# GBxCart_RW_v1_3_Schematic.net
KiCad netlist of a schematic drawn in EAGLE
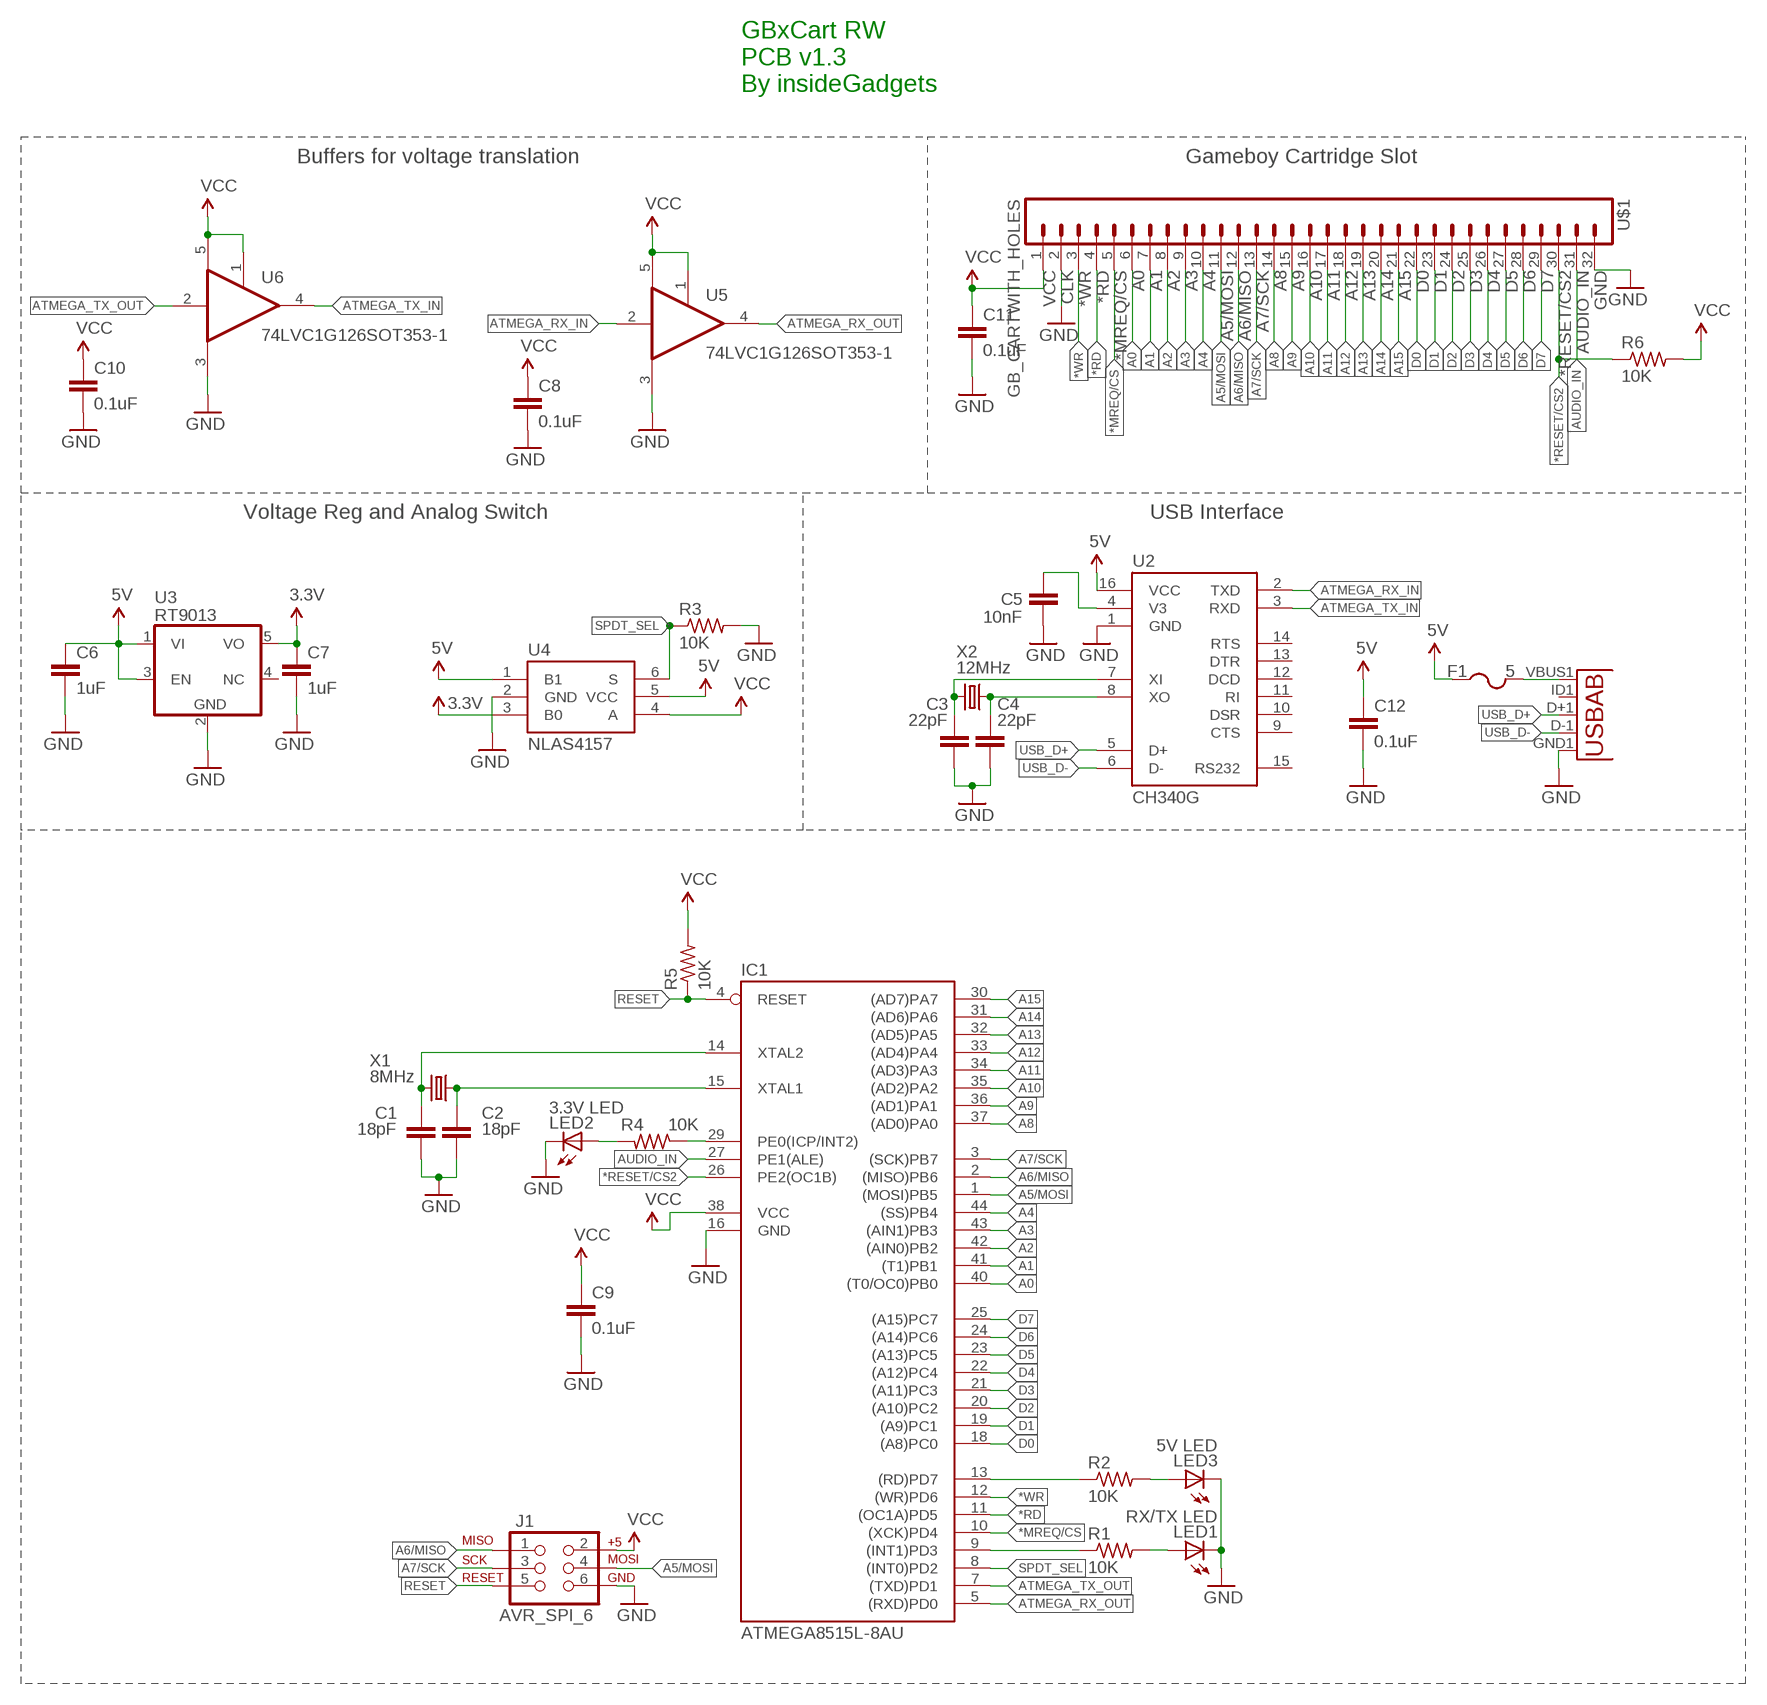
[diagram p0: schematic, sheet 1]

(export (version "E")
  (design (tool "Eeschema 10.0.6"))
  (components
    (comp (ref "C1")
      (value "18pF")
      (footprint "eagle-import:C0805K")
      (libsource (lib "eagle-import") (part "CAP0805"))
    )
    (comp (ref "C2")
      (value "18pF")
      (footprint "eagle-import:C0805K")
      (libsource (lib "eagle-import") (part "CAP0805"))
    )
    (comp (ref "C3")
      (value "22pF")
      (footprint "eagle-import:C0805K")
      (libsource (lib "eagle-import") (part "CAP0805"))
    )
    (comp (ref "C4")
      (value "22pF")
      (footprint "eagle-import:C0805K")
      (libsource (lib "eagle-import") (part "CAP0805"))
    )
    (comp (ref "C5")
      (value "10nF")
      (footprint "eagle-import:C0805K")
      (libsource (lib "eagle-import") (part "CAP0805"))
    )
    (comp (ref "C6")
      (value "1uF")
      (footprint "eagle-import:C0805K")
      (libsource (lib "eagle-import") (part "CAP0805"))
    )
    (comp (ref "C7")
      (value "1uF")
      (footprint "eagle-import:C0805K")
      (libsource (lib "eagle-import") (part "CAP0805"))
    )
    (comp (ref "C8")
      (value "0.1uF")
      (footprint "eagle-import:C0603K")
      (libsource (lib "eagle-import") (part "CAP0603"))
    )
    (comp (ref "C9")
      (value "0.1uF")
      (footprint "eagle-import:C0805K")
      (libsource (lib "eagle-import") (part "CAP0805"))
    )
    (comp (ref "C10")
      (value "0.1uF")
      (footprint "eagle-import:C0603K")
      (libsource (lib "eagle-import") (part "CAP0603"))
    )
    (comp (ref "C11")
      (value "0.1uF")
      (footprint "eagle-import:C0805K")
      (libsource (lib "eagle-import") (part "CAP0805"))
    )
    (comp (ref "C12")
      (value "0.1uF")
      (footprint "eagle-import:C0805K")
      (libsource (lib "eagle-import") (part "CAP0805"))
    )
    (comp (ref "F1")
      (value "5")
      (footprint "eagle-import:R1206")
      (libsource (lib "eagle-import") (part "PTCFUSE-1206"))
    )
    (comp (ref "IC1")
      (value "ATMEGA8515L-8AU")
      (footprint "eagle-import:TQFP44")
      (libsource (lib "eagle-import") (part "MEGA8515-A"))
    )
    (comp (ref "J1")
      (value "AVR_SPI_6")
      (footprint "eagle-import:2X3_2")
      (libsource (lib "eagle-import") (part "AVR_SPI_PRG_6"))
    )
    (comp (ref "LED1")
      (value "RX/TX LED")
      (footprint "eagle-import:CHIP-LED0805-NS")
      (libsource (lib "eagle-import") (part "LEDCHIP-LED0805-NS"))
    )
    (comp (ref "LED2")
      (value "3.3V LED")
      (footprint "eagle-import:CHIP-LED0805-NS")
      (libsource (lib "eagle-import") (part "LEDCHIP-LED0805-NS"))
    )
    (comp (ref "LED3")
      (value "5V LED")
      (footprint "eagle-import:CHIP-LED0805-NS")
      (libsource (lib "eagle-import") (part "LEDCHIP-LED0805-NS"))
    )
    (comp (ref "R1")
      (value "10K")
      (footprint "eagle-import:R0805_2")
      (libsource (lib "eagle-import") (part "R-US_R0805_2"))
    )
    (comp (ref "R2")
      (value "10K")
      (footprint "eagle-import:R0805_2")
      (libsource (lib "eagle-import") (part "R-US_R0805_2"))
    )
    (comp (ref "R3")
      (value "10K")
      (footprint "eagle-import:R0805_2")
      (libsource (lib "eagle-import") (part "R-US_R0805_2"))
    )
    (comp (ref "R4")
      (value "10K")
      (footprint "eagle-import:R0805_2")
      (libsource (lib "eagle-import") (part "R-US_R0805_2"))
    )
    (comp (ref "R5")
      (value "10K")
      (footprint "eagle-import:R0603")
      (libsource (lib "eagle-import") (part "R-US_R0603"))
    )
    (comp (ref "R6")
      (value "10K")
      (footprint "eagle-import:R0805_2")
      (libsource (lib "eagle-import") (part "R-US_R0805_2"))
    )
    (comp (ref "U$1")
      (value "GB_CARTWITH_HOLES")
      (footprint "eagle-import:GB_CART_WHOLES")
      (libsource (lib "eagle-import") (part "GB_CARTWITH_HOLES"))
    )
    (comp (ref "U1")
      (value "USBEP")
      (footprint "eagle-import:USB-MICRO-SMD-EXTRAPADS")
      (libsource (lib "eagle-import") (part "USBEP"))
    )
    (comp (ref "U2")
      (value "CH340G")
      (footprint "eagle-import:SO16")
      (libsource (lib "eagle-import") (part "CH340G"))
    )
    (comp (ref "U3")
      (value "RT9013")
      (footprint "eagle-import:SOT23-5L")
      (libsource (lib "eagle-import") (part "RT9013"))
    )
    (comp (ref "U4")
      (value "NLAS4157")
      (footprint "eagle-import:SOT363")
      (libsource (lib "eagle-import") (part "NLAS4157"))
    )
    (comp (ref "U5")
      (value "74LVC1G126SOT353-1")
      (footprint "eagle-import:SOT353-1")
      (libsource (lib "eagle-import") (part "74LVC1G126SOT353-1"))
    )
    (comp (ref "U6")
      (value "74LVC1G126SOT353-1")
      (footprint "eagle-import:SOT353-1")
      (libsource (lib "eagle-import") (part "74LVC1G126SOT353-1"))
    )
    (comp (ref "X1")
      (value "8MHz")
      (footprint "eagle-import:NX5032")
      (libsource (lib "eagle-import") (part "XTAL-5032"))
    )
    (comp (ref "X2")
      (value "12MHz")
      (footprint "eagle-import:NX5032")
      (libsource (lib "eagle-import") (part "XTAL-5032"))
    )
  )
  (nets
    (net (code "1") (name "*MREQ{slash}CS") (class "Default")
      (node (ref "IC1") (pin "10") (pinfunction "(XCK)PD4_10") (pintype "bidirectional"))
      (node (ref "U$1") (pin "5") (pinfunction "5_5") (pintype "passive"))
    )
    (net (code "2") (name "*RD") (class "Default")
      (node (ref "IC1") (pin "11") (pinfunction "(OC1A)PD5_11") (pintype "bidirectional"))
      (node (ref "U$1") (pin "4") (pinfunction "4_4") (pintype "passive"))
    )
    (net (code "3") (name "*RESET{slash}CS2") (class "Default")
      (node (ref "IC1") (pin "26") (pinfunction "PE2(OC1B)_26") (pintype "bidirectional"))
      (node (ref "R6") (pin "1") (pinfunction "1_1") (pintype "passive"))
      (node (ref "U$1") (pin "30") (pinfunction "30_30") (pintype "passive"))
    )
    (net (code "4") (name "*WR") (class "Default")
      (node (ref "IC1") (pin "12") (pinfunction "(WR)PD6_12") (pintype "bidirectional"))
      (node (ref "U$1") (pin "3") (pinfunction "3_3") (pintype "passive"))
    )
    (net (code "5") (name "3.3V") (class "Default")
      (node (ref "C7") (pin "1") (pinfunction "1_1") (pintype "passive"))
      (node (ref "U3") (pin "5") (pinfunction "VO_5") (pintype "passive"))
      (node (ref "U4") (pin "3") (pinfunction "B0_3") (pintype "bidirectional"))
    )
    (net (code "6") (name "5V") (class "Default")
      (node (ref "C12") (pin "1") (pinfunction "1_1") (pintype "passive"))
      (node (ref "C6") (pin "1") (pinfunction "1_1") (pintype "passive"))
      (node (ref "F1") (pin "1") (pinfunction "1_1") (pintype "passive"))
      (node (ref "U2") (pin "16") (pinfunction "VCC_16") (pintype "power_in"))
      (node (ref "U3") (pin "1") (pinfunction "VI_1") (pintype "input"))
      (node (ref "U3") (pin "3") (pinfunction "EN_3") (pintype "input"))
      (node (ref "U4") (pin "1") (pinfunction "B1_1") (pintype "bidirectional"))
      (node (ref "U4") (pin "5") (pinfunction "VCC_5") (pintype "power_in"))
    )
    (net (code "7") (name "A0") (class "Default")
      (node (ref "IC1") (pin "40") (pinfunction "(T0/OC0)PB0_40") (pintype "bidirectional"))
      (node (ref "U$1") (pin "6") (pinfunction "6_6") (pintype "passive"))
    )
    (net (code "8") (name "A1") (class "Default")
      (node (ref "IC1") (pin "41") (pinfunction "(T1)PB1_41") (pintype "bidirectional"))
      (node (ref "U$1") (pin "7") (pinfunction "7_7") (pintype "passive"))
    )
    (net (code "9") (name "A2") (class "Default")
      (node (ref "IC1") (pin "42") (pinfunction "(AIN0)PB2_42") (pintype "bidirectional"))
      (node (ref "U$1") (pin "8") (pinfunction "8_8") (pintype "passive"))
    )
    (net (code "10") (name "A3") (class "Default")
      (node (ref "IC1") (pin "43") (pinfunction "(AIN1)PB3_43") (pintype "bidirectional"))
      (node (ref "U$1") (pin "9") (pinfunction "9_9") (pintype "passive"))
    )
    (net (code "11") (name "A4") (class "Default")
      (node (ref "IC1") (pin "44") (pinfunction "(SS)PB4_44") (pintype "bidirectional"))
      (node (ref "U$1") (pin "10") (pinfunction "10_10") (pintype "passive"))
    )
    (net (code "12") (name "A5{slash}MOSI") (class "Default")
      (node (ref "IC1") (pin "1") (pinfunction "(MOSI)PB5_1") (pintype "bidirectional"))
      (node (ref "J1") (pin "4") (pinfunction "4_4") (pintype "passive"))
      (node (ref "U$1") (pin "11") (pinfunction "11_11") (pintype "passive"))
    )
    (net (code "13") (name "A6{slash}MISO") (class "Default")
      (node (ref "IC1") (pin "2") (pinfunction "(MISO)PB6_2") (pintype "bidirectional"))
      (node (ref "J1") (pin "1") (pinfunction "1_1") (pintype "passive"))
      (node (ref "U$1") (pin "12") (pinfunction "12_12") (pintype "passive"))
    )
    (net (code "14") (name "A7{slash}SCK") (class "Default")
      (node (ref "IC1") (pin "3") (pinfunction "(SCK)PB7_3") (pintype "bidirectional"))
      (node (ref "J1") (pin "3") (pinfunction "3_3") (pintype "passive"))
      (node (ref "U$1") (pin "13") (pinfunction "13_13") (pintype "passive"))
    )
    (net (code "15") (name "A8") (class "Default")
      (node (ref "IC1") (pin "37") (pinfunction "(AD0)PA0_37") (pintype "bidirectional"))
      (node (ref "U$1") (pin "14") (pinfunction "14_14") (pintype "passive"))
    )
    (net (code "16") (name "A9") (class "Default")
      (node (ref "IC1") (pin "36") (pinfunction "(AD1)PA1_36") (pintype "bidirectional"))
      (node (ref "U$1") (pin "15") (pinfunction "15_15") (pintype "passive"))
    )
    (net (code "17") (name "A10") (class "Default")
      (node (ref "IC1") (pin "35") (pinfunction "(AD2)PA2_35") (pintype "bidirectional"))
      (node (ref "U$1") (pin "16") (pinfunction "16_16") (pintype "passive"))
    )
    (net (code "18") (name "A11") (class "Default")
      (node (ref "IC1") (pin "34") (pinfunction "(AD3)PA3_34") (pintype "bidirectional"))
      (node (ref "U$1") (pin "17") (pinfunction "17_17") (pintype "passive"))
    )
    (net (code "19") (name "A12") (class "Default")
      (node (ref "IC1") (pin "33") (pinfunction "(AD4)PA4_33") (pintype "bidirectional"))
      (node (ref "U$1") (pin "18") (pinfunction "18_18") (pintype "passive"))
    )
    (net (code "20") (name "A13") (class "Default")
      (node (ref "IC1") (pin "32") (pinfunction "(AD5)PA5_32") (pintype "bidirectional"))
      (node (ref "U$1") (pin "19") (pinfunction "19_19") (pintype "passive"))
    )
    (net (code "21") (name "A14") (class "Default")
      (node (ref "IC1") (pin "31") (pinfunction "(AD6)PA6_31") (pintype "bidirectional"))
      (node (ref "U$1") (pin "20") (pinfunction "20_20") (pintype "passive"))
    )
    (net (code "22") (name "A15") (class "Default")
      (node (ref "IC1") (pin "30") (pinfunction "(AD7)PA7_30") (pintype "bidirectional"))
      (node (ref "U$1") (pin "21") (pinfunction "21_21") (pintype "passive"))
    )
    (net (code "23") (name "ATMEGA_RX_IN") (class "Default")
      (node (ref "U2") (pin "2") (pinfunction "TXD_2") (pintype "bidirectional"))
      (node (ref "U5") (pin "2") (pinfunction "I_2") (pintype "input"))
    )
    (net (code "24") (name "ATMEGA_RX_OUT") (class "Default")
      (node (ref "IC1") (pin "5") (pinfunction "(RXD)PD0_5") (pintype "bidirectional"))
      (node (ref "U5") (pin "4") (pinfunction "O_4") (pintype "output"))
    )
    (net (code "25") (name "ATMEGA_TX_IN") (class "Default")
      (node (ref "U2") (pin "3") (pinfunction "RXD_3") (pintype "bidirectional"))
      (node (ref "U6") (pin "4") (pinfunction "O_4") (pintype "output"))
    )
    (net (code "26") (name "ATMEGA_TX_OUT") (class "Default")
      (node (ref "IC1") (pin "7") (pinfunction "(TXD)PD1_7") (pintype "bidirectional"))
      (node (ref "U6") (pin "2") (pinfunction "I_2") (pintype "input"))
    )
    (net (code "27") (name "AUDIO_IN") (class "Default")
      (node (ref "IC1") (pin "27") (pinfunction "PE1(ALE)_27") (pintype "bidirectional"))
      (node (ref "U$1") (pin "31") (pinfunction "31_31") (pintype "passive"))
    )
    (net (code "28") (name "D0") (class "Default")
      (node (ref "IC1") (pin "18") (pinfunction "(A8)PC0_18") (pintype "bidirectional"))
      (node (ref "U$1") (pin "22") (pinfunction "22_22") (pintype "passive"))
    )
    (net (code "29") (name "D1") (class "Default")
      (node (ref "IC1") (pin "19") (pinfunction "(A9)PC1_19") (pintype "bidirectional"))
      (node (ref "U$1") (pin "23") (pinfunction "23_23") (pintype "passive"))
    )
    (net (code "30") (name "D2") (class "Default")
      (node (ref "IC1") (pin "20") (pinfunction "(A10)PC2_20") (pintype "bidirectional"))
      (node (ref "U$1") (pin "24") (pinfunction "24_24") (pintype "passive"))
    )
    (net (code "31") (name "D3") (class "Default")
      (node (ref "IC1") (pin "21") (pinfunction "(A11)PC3_21") (pintype "bidirectional"))
      (node (ref "U$1") (pin "25") (pinfunction "25_25") (pintype "passive"))
    )
    (net (code "32") (name "D4") (class "Default")
      (node (ref "IC1") (pin "22") (pinfunction "(A12)PC4_22") (pintype "bidirectional"))
      (node (ref "U$1") (pin "26") (pinfunction "26_26") (pintype "passive"))
    )
    (net (code "33") (name "D5") (class "Default")
      (node (ref "IC1") (pin "23") (pinfunction "(A13)PC5_23") (pintype "bidirectional"))
      (node (ref "U$1") (pin "27") (pinfunction "27_27") (pintype "passive"))
    )
    (net (code "34") (name "D6") (class "Default")
      (node (ref "IC1") (pin "24") (pinfunction "(A14)PC6_24") (pintype "bidirectional"))
      (node (ref "U$1") (pin "28") (pinfunction "28_28") (pintype "passive"))
    )
    (net (code "35") (name "D7") (class "Default")
      (node (ref "IC1") (pin "25") (pinfunction "(A15)PC7_25") (pintype "bidirectional"))
      (node (ref "U$1") (pin "29") (pinfunction "29_29") (pintype "passive"))
    )
    (net (code "36") (name "GND") (class "Default")
      (node (ref "C1") (pin "2") (pinfunction "2_2") (pintype "passive"))
      (node (ref "C10") (pin "2") (pinfunction "2_2") (pintype "passive"))
      (node (ref "C11") (pin "2") (pinfunction "2_2") (pintype "passive"))
      (node (ref "C12") (pin "2") (pinfunction "2_2") (pintype "passive"))
      (node (ref "C2") (pin "2") (pinfunction "2_2") (pintype "passive"))
      (node (ref "C3") (pin "2") (pinfunction "2_2") (pintype "passive"))
      (node (ref "C4") (pin "2") (pinfunction "2_2") (pintype "passive"))
      (node (ref "C5") (pin "2") (pinfunction "2_2") (pintype "passive"))
      (node (ref "C6") (pin "2") (pinfunction "2_2") (pintype "passive"))
      (node (ref "C7") (pin "2") (pinfunction "2_2") (pintype "passive"))
      (node (ref "C8") (pin "2") (pinfunction "2_2") (pintype "passive"))
      (node (ref "C9") (pin "2") (pinfunction "2_2") (pintype "passive"))
      (node (ref "IC1") (pin "16") (pinfunction "GND_16") (pintype "power_in"))
      (node (ref "J1") (pin "6") (pinfunction "6_6") (pintype "passive"))
      (node (ref "LED1") (pin "C") (pinfunction "C_C") (pintype "passive"))
      (node (ref "LED2") (pin "C") (pinfunction "C_C") (pintype "passive"))
      (node (ref "LED3") (pin "C") (pinfunction "C_C") (pintype "passive"))
      (node (ref "R3") (pin "2") (pinfunction "2_2") (pintype "passive"))
      (node (ref "U$1") (pin "2") (pinfunction "2_2") (pintype "passive"))
      (node (ref "U$1") (pin "32") (pinfunction "32_32") (pintype "passive"))
      (node (ref "U1") (pin "GND1") (pinfunction "GND_GND1") (pintype "bidirectional"))
      (node (ref "U2") (pin "1") (pinfunction "GND_1") (pintype "power_in"))
      (node (ref "U3") (pin "2") (pinfunction "GND_2") (pintype "passive"))
      (node (ref "U4") (pin "2") (pinfunction "GND_2") (pintype "power_in"))
      (node (ref "U5") (pin "3") (pinfunction "GND_3") (pintype "power_in"))
      (node (ref "U6") (pin "3") (pinfunction "GND_3") (pintype "power_in"))
    )
    (net (code "37") (name "Net-(IC1-(INT1)PD3)") (class "Default")
      (node (ref "IC1") (pin "9") (pinfunction "(INT1)PD3_9") (pintype "bidirectional"))
      (node (ref "R1") (pin "1") (pinfunction "1_1") (pintype "passive"))
    )
    (net (code "38") (name "Net-(IC1-(RD)PD7)") (class "Default")
      (node (ref "IC1") (pin "13") (pinfunction "(RD)PD7_13") (pintype "bidirectional"))
      (node (ref "R2") (pin "1") (pinfunction "1_1") (pintype "passive"))
    )
    (net (code "39") (name "Net-(IC1-PE0(ICP{slash}INT2))") (class "Default")
      (node (ref "IC1") (pin "29") (pinfunction "PE0(ICP/INT2)_29") (pintype "bidirectional"))
      (node (ref "R4") (pin "1") (pinfunction "1_1") (pintype "passive"))
    )
    (net (code "40") (name "Net-(IC1-XTAL1)") (class "Default")
      (node (ref "C2") (pin "1") (pinfunction "1_1") (pintype "passive"))
      (node (ref "IC1") (pin "15") (pinfunction "XTAL1_15") (pintype "bidirectional"))
      (node (ref "X1") (pin "P$1") (pinfunction "1_P$1") (pintype "passive"))
    )
    (net (code "41") (name "Net-(IC1-XTAL2)") (class "Default")
      (node (ref "C1") (pin "1") (pinfunction "1_1") (pintype "passive"))
      (node (ref "IC1") (pin "14") (pinfunction "XTAL2_14") (pintype "bidirectional"))
      (node (ref "X1") (pin "P$2") (pinfunction "2_P$2") (pintype "passive"))
    )
    (net (code "42") (name "Net-(LED1-PadA)") (class "Default")
      (node (ref "LED1") (pin "A") (pinfunction "A_A") (pintype "passive"))
      (node (ref "R1") (pin "2") (pinfunction "2_2") (pintype "passive"))
    )
    (net (code "43") (name "Net-(LED2-PadA)") (class "Default")
      (node (ref "LED2") (pin "A") (pinfunction "A_A") (pintype "passive"))
      (node (ref "R4") (pin "2") (pinfunction "2_2") (pintype "passive"))
    )
    (net (code "44") (name "Net-(LED3-PadA)") (class "Default")
      (node (ref "LED3") (pin "A") (pinfunction "A_A") (pintype "passive"))
      (node (ref "R2") (pin "2") (pinfunction "2_2") (pintype "passive"))
    )
    (net (code "45") (name "Net-(U1-VBUS)") (class "Default")
      (node (ref "F1") (pin "2") (pinfunction "2_2") (pintype "passive"))
      (node (ref "U1") (pin "VBUS1") (pinfunction "VBUS_VBUS1") (pintype "bidirectional"))
    )
    (net (code "46") (name "Net-(U2-V3)") (class "Default")
      (node (ref "C5") (pin "1") (pinfunction "1_1") (pintype "passive"))
      (node (ref "U2") (pin "4") (pinfunction "V3_4") (pintype "power_in"))
    )
    (net (code "47") (name "Net-(U2-XI)") (class "Default")
      (node (ref "C3") (pin "1") (pinfunction "1_1") (pintype "passive"))
      (node (ref "U2") (pin "7") (pinfunction "XI_7") (pintype "bidirectional"))
      (node (ref "X2") (pin "P$2") (pinfunction "2_P$2") (pintype "passive"))
    )
    (net (code "48") (name "Net-(U2-XO)") (class "Default")
      (node (ref "C4") (pin "1") (pinfunction "1_1") (pintype "passive"))
      (node (ref "U2") (pin "8") (pinfunction "XO_8") (pintype "bidirectional"))
      (node (ref "X2") (pin "P$1") (pinfunction "1_P$1") (pintype "passive"))
    )
    (net (code "49") (name "RESET") (class "Default")
      (node (ref "IC1") (pin "4") (pinfunction "RESET_4") (pintype "input"))
      (node (ref "J1") (pin "5") (pinfunction "5_5") (pintype "passive"))
      (node (ref "R5") (pin "1") (pinfunction "1_1") (pintype "passive"))
    )
    (net (code "50") (name "SPDT_SEL") (class "Default")
      (node (ref "IC1") (pin "8") (pinfunction "(INT0)PD2_8") (pintype "bidirectional"))
      (node (ref "R3") (pin "1") (pinfunction "1_1") (pintype "passive"))
      (node (ref "U4") (pin "6") (pinfunction "S_6") (pintype "bidirectional"))
    )
    (net (code "51") (name "USB_D+") (class "Default")
      (node (ref "U1") (pin "D+1") (pinfunction "D+_D+1") (pintype "bidirectional"))
      (node (ref "U2") (pin "5") (pinfunction "D+_5") (pintype "bidirectional"))
    )
    (net (code "52") (name "USB_D-") (class "Default")
      (node (ref "U1") (pin "D-1") (pinfunction "D-_D-1") (pintype "bidirectional"))
      (node (ref "U2") (pin "6") (pinfunction "D-_6") (pintype "bidirectional"))
    )
    (net (code "53") (name "VCC") (class "Default")
      (node (ref "C10") (pin "1") (pinfunction "1_1") (pintype "passive"))
      (node (ref "C11") (pin "1") (pinfunction "1_1") (pintype "passive"))
      (node (ref "C8") (pin "1") (pinfunction "1_1") (pintype "passive"))
      (node (ref "C9") (pin "1") (pinfunction "1_1") (pintype "passive"))
      (node (ref "IC1") (pin "38") (pinfunction "VCC_38") (pintype "power_in"))
      (node (ref "J1") (pin "2") (pinfunction "2_2") (pintype "passive"))
      (node (ref "R5") (pin "2") (pinfunction "2_2") (pintype "passive"))
      (node (ref "R6") (pin "2") (pinfunction "2_2") (pintype "passive"))
      (node (ref "U$1") (pin "1") (pinfunction "1_1") (pintype "passive"))
      (node (ref "U4") (pin "4") (pinfunction "A_4") (pintype "bidirectional"))
      (node (ref "U5") (pin "1") (pinfunction "OE_1") (pintype "input"))
      (node (ref "U5") (pin "5") (pinfunction "VCC_5") (pintype "power_in"))
      (node (ref "U6") (pin "1") (pinfunction "OE_1") (pintype "input"))
      (node (ref "U6") (pin "5") (pinfunction "VCC_5") (pintype "power_in"))
    )
    (net (code "54") (name "unconnected-(IC1-NC1-Pad6)") (class "Default")
      (node (ref "IC1") (pin "6") (pinfunction "NC1_6") (pintype "no_connect"))
    )
    (net (code "55") (name "unconnected-(IC1-NC2-Pad17)") (class "Default")
      (node (ref "IC1") (pin "17") (pinfunction "NC2_17") (pintype "no_connect"))
    )
    (net (code "56") (name "unconnected-(IC1-NC3-Pad28)") (class "Default")
      (node (ref "IC1") (pin "28") (pinfunction "NC3_28") (pintype "no_connect"))
    )
    (net (code "57") (name "unconnected-(IC1-NC4-Pad39)") (class "Default")
      (node (ref "IC1") (pin "39") (pinfunction "NC4_39") (pintype "no_connect"))
    )
    (net (code "58") (name "unconnected-(U1-USBID-PadID1)") (class "Default")
      (node (ref "U1") (pin "ID1") (pinfunction "USBID_ID1") (pintype "bidirectional"))
    )
    (net (code "59") (name "unconnected-(U2-CTS-Pad9)") (class "Default")
      (node (ref "U2") (pin "9") (pinfunction "CTS_9") (pintype "bidirectional"))
    )
    (net (code "60") (name "unconnected-(U2-DCD-Pad12)") (class "Default")
      (node (ref "U2") (pin "12") (pinfunction "DCD_12") (pintype "bidirectional"))
    )
    (net (code "61") (name "unconnected-(U2-DSR-Pad10)") (class "Default")
      (node (ref "U2") (pin "10") (pinfunction "DSR_10") (pintype "bidirectional"))
    )
    (net (code "62") (name "unconnected-(U2-DTR-Pad13)") (class "Default")
      (node (ref "U2") (pin "13") (pinfunction "DTR_13") (pintype "bidirectional"))
    )
    (net (code "63") (name "unconnected-(U2-RI-Pad11)") (class "Default")
      (node (ref "U2") (pin "11") (pinfunction "RI_11") (pintype "bidirectional"))
    )
    (net (code "64") (name "unconnected-(U2-RS232-Pad15)") (class "Default")
      (node (ref "U2") (pin "15") (pinfunction "RS232_15") (pintype "bidirectional"))
    )
    (net (code "65") (name "unconnected-(U2-RTS-Pad14)") (class "Default")
      (node (ref "U2") (pin "14") (pinfunction "RTS_14") (pintype "bidirectional"))
    )
    (net (code "66") (name "unconnected-(U3-NC-Pad4)") (class "Default")
      (node (ref "U3") (pin "4") (pinfunction "NC_4") (pintype "no_connect"))
    )
  )
)
